# 3_-MCU_MAIN.net
KiCad netlist of a schematic drawn in Altium Designer
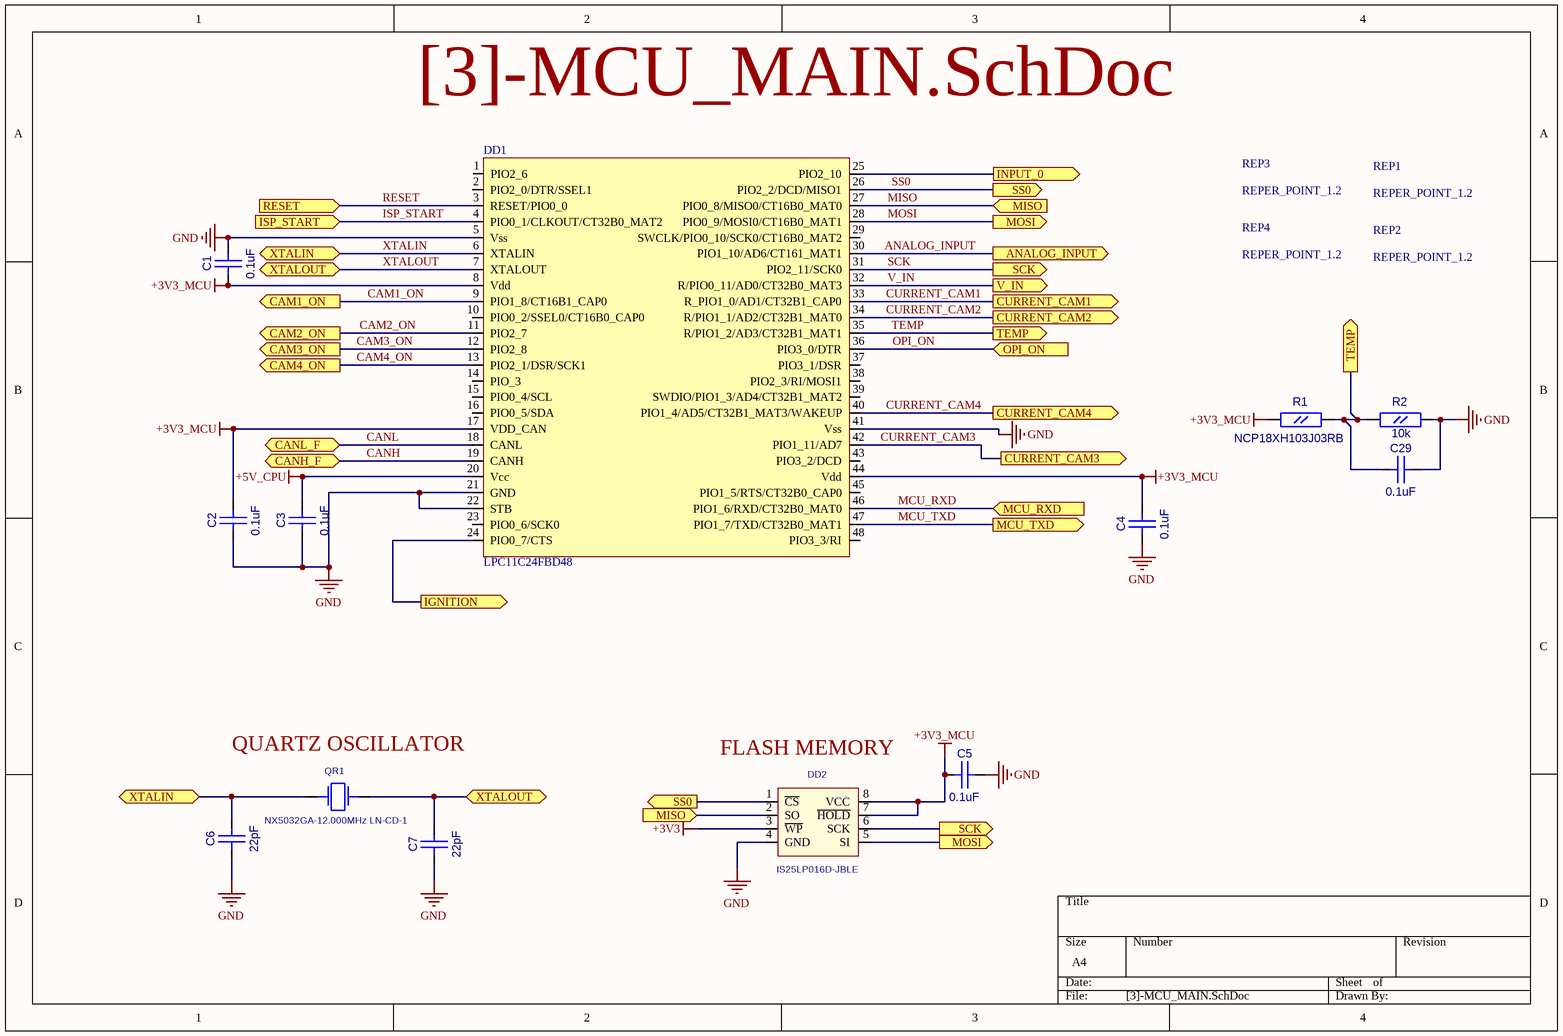
[diagram p0: [3]-MCU_MAIN.SchDoc]

(export (version "E")
  (design (tool "Eeschema 10.0.6"))
  (components
    (comp (ref "C1")
      (value "0.1uF")
      (footprint "CC0603")
      (description "CC0603")
      (libsource (lib "fizik_lib") (part "CC0603"))
    )
    (comp (ref "C2")
      (value "0.1uF")
      (footprint "CC0603")
      (description "CC0603")
      (libsource (lib "fizik_lib") (part "CC0603"))
    )
    (comp (ref "C3")
      (value "0.1uF")
      (footprint "CC0603")
      (description "CC0603")
      (libsource (lib "fizik_lib") (part "CC0603"))
    )
    (comp (ref "C4")
      (value "0.1uF")
      (footprint "CC0603")
      (description "CC0603")
      (libsource (lib "fizik_lib") (part "CC0603"))
    )
    (comp (ref "C5")
      (value "0.1uF")
      (footprint "CC0603")
      (description "CC0603")
      (libsource (lib "gprs_modem_2") (part "CC0603"))
    )
    (comp (ref "C6")
      (value "22pF")
      (footprint "CC0603")
      (description "CC0603")
      (libsource (lib "gprs_modem_2") (part "CC0603"))
    )
    (comp (ref "C7")
      (value "22pF")
      (footprint "CC0603")
      (description "CC0603")
      (libsource (lib "gprs_modem_2") (part "CC0603"))
    )
    (comp (ref "C29")
      (value "0.1uF")
      (footprint "CC0603")
      (description "CC0603")
      (libsource (lib "fizik_lib") (part "CC0603"))
    )
    (comp (ref "DD1")
      (value "LPC11C24FBD48")
      (footprint "LQFP48")
      (libsource (lib "fizik_lib") (part "LPC11C24FBD48"))
    )
    (comp (ref "DD2")
      (value "IS25LP016D-JBLE")
      (footprint "EIAJ_SO8")
      (description "S25FL016A0LMFI01")
      (libsource (lib "gprs_modem_2") (part "S25FL016A0LMFI01"))
    )
    (comp (ref "QR1")
      (value "NX5032GA-12.000MHz LN-CD-1")
      (footprint "AC5032_2")
      (description "AC5032/2")
      (libsource (lib "gprs_modem_2") (part "AC5032_2"))
    )
    (comp (ref "R1")
      (value "NCP18XH103J03RB")
      (footprint "RC0603")
      (description "RC0603")
      (libsource (lib "fizik_lib") (part "RC0603"))
    )
    (comp (ref "R2")
      (value "10k")
      (footprint "RC0603")
      (description "RC0603")
      (libsource (lib "fizik_lib") (part "RC0603"))
    )
    (comp (ref "REP1")
      (value "REPER_POINT_1.2")
      (footprint "REPER1.2")
      (description "REPER1.2")
      (libsource (lib "fizik_lib") (part "REPER1.2"))
    )
    (comp (ref "REP2")
      (value "REPER_POINT_1.2")
      (footprint "REPER1.2")
      (description "REPER1.2")
      (libsource (lib "fizik_lib") (part "REPER1.2"))
    )
    (comp (ref "REP3")
      (value "REPER_POINT_1.2")
      (footprint "REPER1.2")
      (description "REPER1.2")
      (libsource (lib "fizik_lib") (part "REPER1.2"))
    )
    (comp (ref "REP4")
      (value "REPER_POINT_1.2")
      (footprint "REPER1.2")
      (description "REPER1.2")
      (libsource (lib "fizik_lib") (part "REPER1.2"))
    )
  )
  (nets
    (net (code "1") (name "+3V3") (class "Default")
      (node (ref "DD2") (pin "3") (pinfunction "~{WP}_3") (pintype "passive"))
    )
    (net (code "2") (name "+3V3_MCU") (class "Default")
      (node (ref "C1") (pin "1") (pinfunction "A_1") (pintype "passive"))
      (node (ref "C2") (pin "2") (pinfunction "B_2") (pintype "passive"))
      (node (ref "C4") (pin "2") (pinfunction "B_2") (pintype "passive"))
      (node (ref "C5") (pin "1") (pinfunction "A_1") (pintype "passive"))
      (node (ref "DD1") (pin "17") (pinfunction "VDD_CAN_17") (pintype "passive"))
      (node (ref "DD1") (pin "44") (pinfunction "Vdd_44") (pintype "passive"))
      (node (ref "DD1") (pin "8") (pinfunction "Vdd_8") (pintype "passive"))
      (node (ref "DD2") (pin "7") (pinfunction "~{HOLD}_7") (pintype "passive"))
      (node (ref "DD2") (pin "8") (pinfunction "VCC_8") (pintype "passive"))
      (node (ref "R1") (pin "1") (pinfunction "A_1") (pintype "passive"))
    )
    (net (code "3") (name "+5V_CPU") (class "Default")
      (node (ref "C3") (pin "2") (pinfunction "B_2") (pintype "passive"))
      (node (ref "DD1") (pin "20") (pinfunction "Vcc_20") (pintype "passive"))
    )
    (net (code "4") (name "/ANALOG_INPUT") (class "Default")
      (node (ref "DD1") (pin "30") (pinfunction "PIO1_10/AD6/CT161_MAT1_30") (pintype "passive"))
    )
    (net (code "5") (name "/CAM1_ON") (class "Default")
      (node (ref "DD1") (pin "9") (pinfunction "PIO1_8/CT16B1_CAP0_9") (pintype "passive"))
    )
    (net (code "6") (name "/CAM2_ON") (class "Default")
      (node (ref "DD1") (pin "11") (pinfunction "PIO2_7_11") (pintype "passive"))
    )
    (net (code "7") (name "/CAM3_ON") (class "Default")
      (node (ref "DD1") (pin "12") (pinfunction "PIO2_8_12") (pintype "passive"))
    )
    (net (code "8") (name "/CAM4_ON") (class "Default")
      (node (ref "DD1") (pin "13") (pinfunction "PIO2_1/DSR/SCK1_13") (pintype "passive"))
    )
    (net (code "9") (name "/CANH") (class "Default")
      (node (ref "DD1") (pin "19") (pinfunction "CANH_19") (pintype "passive"))
    )
    (net (code "10") (name "/CANL") (class "Default")
      (node (ref "DD1") (pin "18") (pinfunction "CANL_18") (pintype "passive"))
    )
    (net (code "11") (name "/CURRENT_CAM1") (class "Default")
      (node (ref "DD1") (pin "33") (pinfunction "R_PIO1_0/AD1/CT32B1_CAP0_33") (pintype "passive"))
    )
    (net (code "12") (name "/CURRENT_CAM2") (class "Default")
      (node (ref "DD1") (pin "34") (pinfunction "R/PIO1_1/AD2/CT32B1_MAT0_34") (pintype "passive"))
    )
    (net (code "13") (name "/CURRENT_CAM3") (class "Default")
      (node (ref "DD1") (pin "42") (pinfunction "PIO1_11/AD7_42") (pintype "passive"))
    )
    (net (code "14") (name "/CURRENT_CAM4") (class "Default")
      (node (ref "DD1") (pin "40") (pinfunction "PIO1_4/AD5/CT32B1_MAT3/WAKEUP_40") (pintype "passive"))
    )
    (net (code "15") (name "/IGNITION") (class "Default")
      (node (ref "DD1") (pin "24") (pinfunction "PIO0_7/CTS_24") (pintype "passive"))
    )
    (net (code "16") (name "/INPUT_0") (class "Default")
      (node (ref "DD1") (pin "25") (pinfunction "PIO2_10_25") (pintype "passive"))
    )
    (net (code "17") (name "/ISP_START") (class "Default")
      (node (ref "DD1") (pin "4") (pinfunction "PIO0_1/CLKOUT/CT32B0_MAT2_4") (pintype "passive"))
    )
    (net (code "18") (name "/MCU_RXD") (class "Default")
      (node (ref "DD1") (pin "46") (pinfunction "PIO1_6/RXD/CT32B0_MAT0_46") (pintype "passive"))
    )
    (net (code "19") (name "/MCU_TXD") (class "Default")
      (node (ref "DD1") (pin "47") (pinfunction "PIO1_7/TXD/CT32B0_MAT1_47") (pintype "passive"))
    )
    (net (code "20") (name "/MISO") (class "Default")
      (node (ref "DD1") (pin "27") (pinfunction "PIO0_8/MISO0/CT16B0_MAT0_27") (pintype "passive"))
      (node (ref "DD2") (pin "2") (pinfunction "SO_2") (pintype "passive"))
    )
    (net (code "21") (name "/MOSI") (class "Default")
      (node (ref "DD1") (pin "28") (pinfunction "PIO0_9/MOSI0/CT16B0_MAT1_28") (pintype "passive"))
      (node (ref "DD2") (pin "5") (pinfunction "SI_5") (pintype "passive"))
    )
    (net (code "22") (name "/OPI_ON") (class "Default")
      (node (ref "DD1") (pin "36") (pinfunction "PIO3_0/DTR_36") (pintype "passive"))
    )
    (net (code "23") (name "/RESET") (class "Default")
      (node (ref "DD1") (pin "3") (pinfunction "RESET/PIO0_0_3") (pintype "passive"))
    )
    (net (code "24") (name "/SCK") (class "Default")
      (node (ref "DD1") (pin "31") (pinfunction "PIO2_11/SCK0_31") (pintype "passive"))
      (node (ref "DD2") (pin "6") (pinfunction "SCK_6") (pintype "passive"))
    )
    (net (code "25") (name "/SS0") (class "Default")
      (node (ref "DD1") (pin "26") (pinfunction "PIO2_2/DCD/MISO1_26") (pintype "passive"))
      (node (ref "DD2") (pin "1") (pinfunction "~{CS}_1") (pintype "passive"))
    )
    (net (code "26") (name "/TEMP") (class "Default")
      (node (ref "C29") (pin "1") (pinfunction "A_1") (pintype "passive"))
      (node (ref "DD1") (pin "35") (pinfunction "R/PIO1_2/AD3/CT32B1_MAT1_35") (pintype "passive"))
      (node (ref "R1") (pin "2") (pinfunction "B_2") (pintype "passive"))
      (node (ref "R2") (pin "1") (pinfunction "A_1") (pintype "passive"))
    )
    (net (code "27") (name "/V_IN") (class "Default")
      (node (ref "DD1") (pin "32") (pinfunction "R/PIO0_11/AD0/CT32B0_MAT3_32") (pintype "passive"))
    )
    (net (code "28") (name "/XTALIN") (class "Default")
      (node (ref "C6") (pin "2") (pinfunction "B_2") (pintype "passive"))
      (node (ref "DD1") (pin "6") (pinfunction "XTALIN_6") (pintype "passive"))
      (node (ref "QR1") (pin "1") (pintype "passive"))
    )
    (net (code "29") (name "/XTALOUT") (class "Default")
      (node (ref "C7") (pin "2") (pinfunction "B_2") (pintype "passive"))
      (node (ref "DD1") (pin "7") (pinfunction "XTALOUT_7") (pintype "passive"))
      (node (ref "QR1") (pin "2") (pintype "passive"))
    )
    (net (code "30") (name "GND") (class "Default")
      (node (ref "C1") (pin "2") (pinfunction "B_2") (pintype "passive"))
      (node (ref "C2") (pin "1") (pinfunction "A_1") (pintype "passive"))
      (node (ref "C29") (pin "2") (pinfunction "B_2") (pintype "passive"))
      (node (ref "C3") (pin "1") (pinfunction "A_1") (pintype "passive"))
      (node (ref "C4") (pin "1") (pinfunction "A_1") (pintype "passive"))
      (node (ref "C5") (pin "2") (pinfunction "B_2") (pintype "passive"))
      (node (ref "C6") (pin "1") (pinfunction "A_1") (pintype "passive"))
      (node (ref "C7") (pin "1") (pinfunction "A_1") (pintype "passive"))
      (node (ref "DD1") (pin "21") (pinfunction "GND_21") (pintype "passive"))
      (node (ref "DD1") (pin "22") (pinfunction "STB_22") (pintype "passive"))
      (node (ref "DD1") (pin "41") (pinfunction "Vss_41") (pintype "passive"))
      (node (ref "DD1") (pin "5") (pinfunction "Vss_5") (pintype "passive"))
      (node (ref "DD2") (pin "4") (pinfunction "GND_4") (pintype "passive"))
      (node (ref "R2") (pin "2") (pinfunction "B_2") (pintype "passive"))
    )
    (net (code "31") (name "unconnected-(DD1-PIO0_2{slash}SSEL0{slash}CT16B0_CAP0-Pad10)") (class "Default")
      (node (ref "DD1") (pin "10") (pinfunction "PIO0_2/SSEL0/CT16B0_CAP0_10") (pintype "passive"))
    )
    (net (code "32") (name "unconnected-(DD1-PIO0_4{slash}SCL-Pad15)") (class "Default")
      (node (ref "DD1") (pin "15") (pinfunction "PIO0_4/SCL_15") (pintype "passive"))
    )
    (net (code "33") (name "unconnected-(DD1-PIO0_5{slash}SDA-Pad16)") (class "Default")
      (node (ref "DD1") (pin "16") (pinfunction "PIO0_5/SDA_16") (pintype "passive"))
    )
    (net (code "34") (name "unconnected-(DD1-PIO0_6{slash}SCK0-Pad23)") (class "Default")
      (node (ref "DD1") (pin "23") (pinfunction "PIO0_6/SCK0_23") (pintype "passive"))
    )
    (net (code "35") (name "unconnected-(DD1-PIO1_5{slash}RTS{slash}CT32B0_CAP0-Pad45)") (class "Default")
      (node (ref "DD1") (pin "45") (pinfunction "PIO1_5/RTS/CT32B0_CAP0_45") (pintype "passive"))
    )
    (net (code "36") (name "unconnected-(DD1-PIO2_0{slash}DTR{slash}SSEL1-Pad2)") (class "Default")
      (node (ref "DD1") (pin "2") (pinfunction "PIO2_0/DTR/SSEL1_2") (pintype "passive"))
    )
    (net (code "37") (name "unconnected-(DD1-PIO2_3{slash}RI{slash}MOSI1-Pad38)") (class "Default")
      (node (ref "DD1") (pin "38") (pinfunction "PIO2_3/RI/MOSI1_38") (pintype "passive"))
    )
    (net (code "38") (name "unconnected-(DD1-PIO2_6-Pad1)") (class "Default")
      (node (ref "DD1") (pin "1") (pinfunction "PIO2_6_1") (pintype "passive"))
    )
    (net (code "39") (name "unconnected-(DD1-PIO3_1{slash}DSR-Pad37)") (class "Default")
      (node (ref "DD1") (pin "37") (pinfunction "PIO3_1/DSR_37") (pintype "passive"))
    )
    (net (code "40") (name "unconnected-(DD1-PIO3_2{slash}DCD-Pad43)") (class "Default")
      (node (ref "DD1") (pin "43") (pinfunction "PIO3_2/DCD_43") (pintype "passive"))
    )
    (net (code "41") (name "unconnected-(DD1-PIO3_3{slash}RI-Pad48)") (class "Default")
      (node (ref "DD1") (pin "48") (pinfunction "PIO3_3/RI_48") (pintype "passive"))
    )
    (net (code "42") (name "unconnected-(DD1-PIO_3-Pad14)") (class "Default")
      (node (ref "DD1") (pin "14") (pinfunction "PIO_3_14") (pintype "passive"))
    )
    (net (code "43") (name "unconnected-(DD1-SWCLK{slash}PIO0_10{slash}SCK0{slash}CT16B0_MAT2-Pad29)") (class "Default")
      (node (ref "DD1") (pin "29") (pinfunction "SWCLK/PIO0_10/SCK0/CT16B0_MAT2_29") (pintype "passive"))
    )
    (net (code "44") (name "unconnected-(DD1-SWDIO{slash}PIO1_3{slash}AD4{slash}CT32B1_MAT2-Pad39)") (class "Default")
      (node (ref "DD1") (pin "39") (pinfunction "SWDIO/PIO1_3/AD4/CT32B1_MAT2_39") (pintype "passive"))
    )
    (net (code "45") (name "unconnected-(REP1-Pad1)") (class "Default")
      (node (ref "REP1") (pin "1") (pintype "passive"))
    )
    (net (code "46") (name "unconnected-(REP2-Pad1)") (class "Default")
      (node (ref "REP2") (pin "1") (pintype "passive"))
    )
    (net (code "47") (name "unconnected-(REP3-Pad1)") (class "Default")
      (node (ref "REP3") (pin "1") (pintype "passive"))
    )
    (net (code "48") (name "unconnected-(REP4-Pad1)") (class "Default")
      (node (ref "REP4") (pin "1") (pintype "passive"))
    )
  )
)
